# Ethernet3.net
KiCad netlist of a schematic drawn in Altium Designer
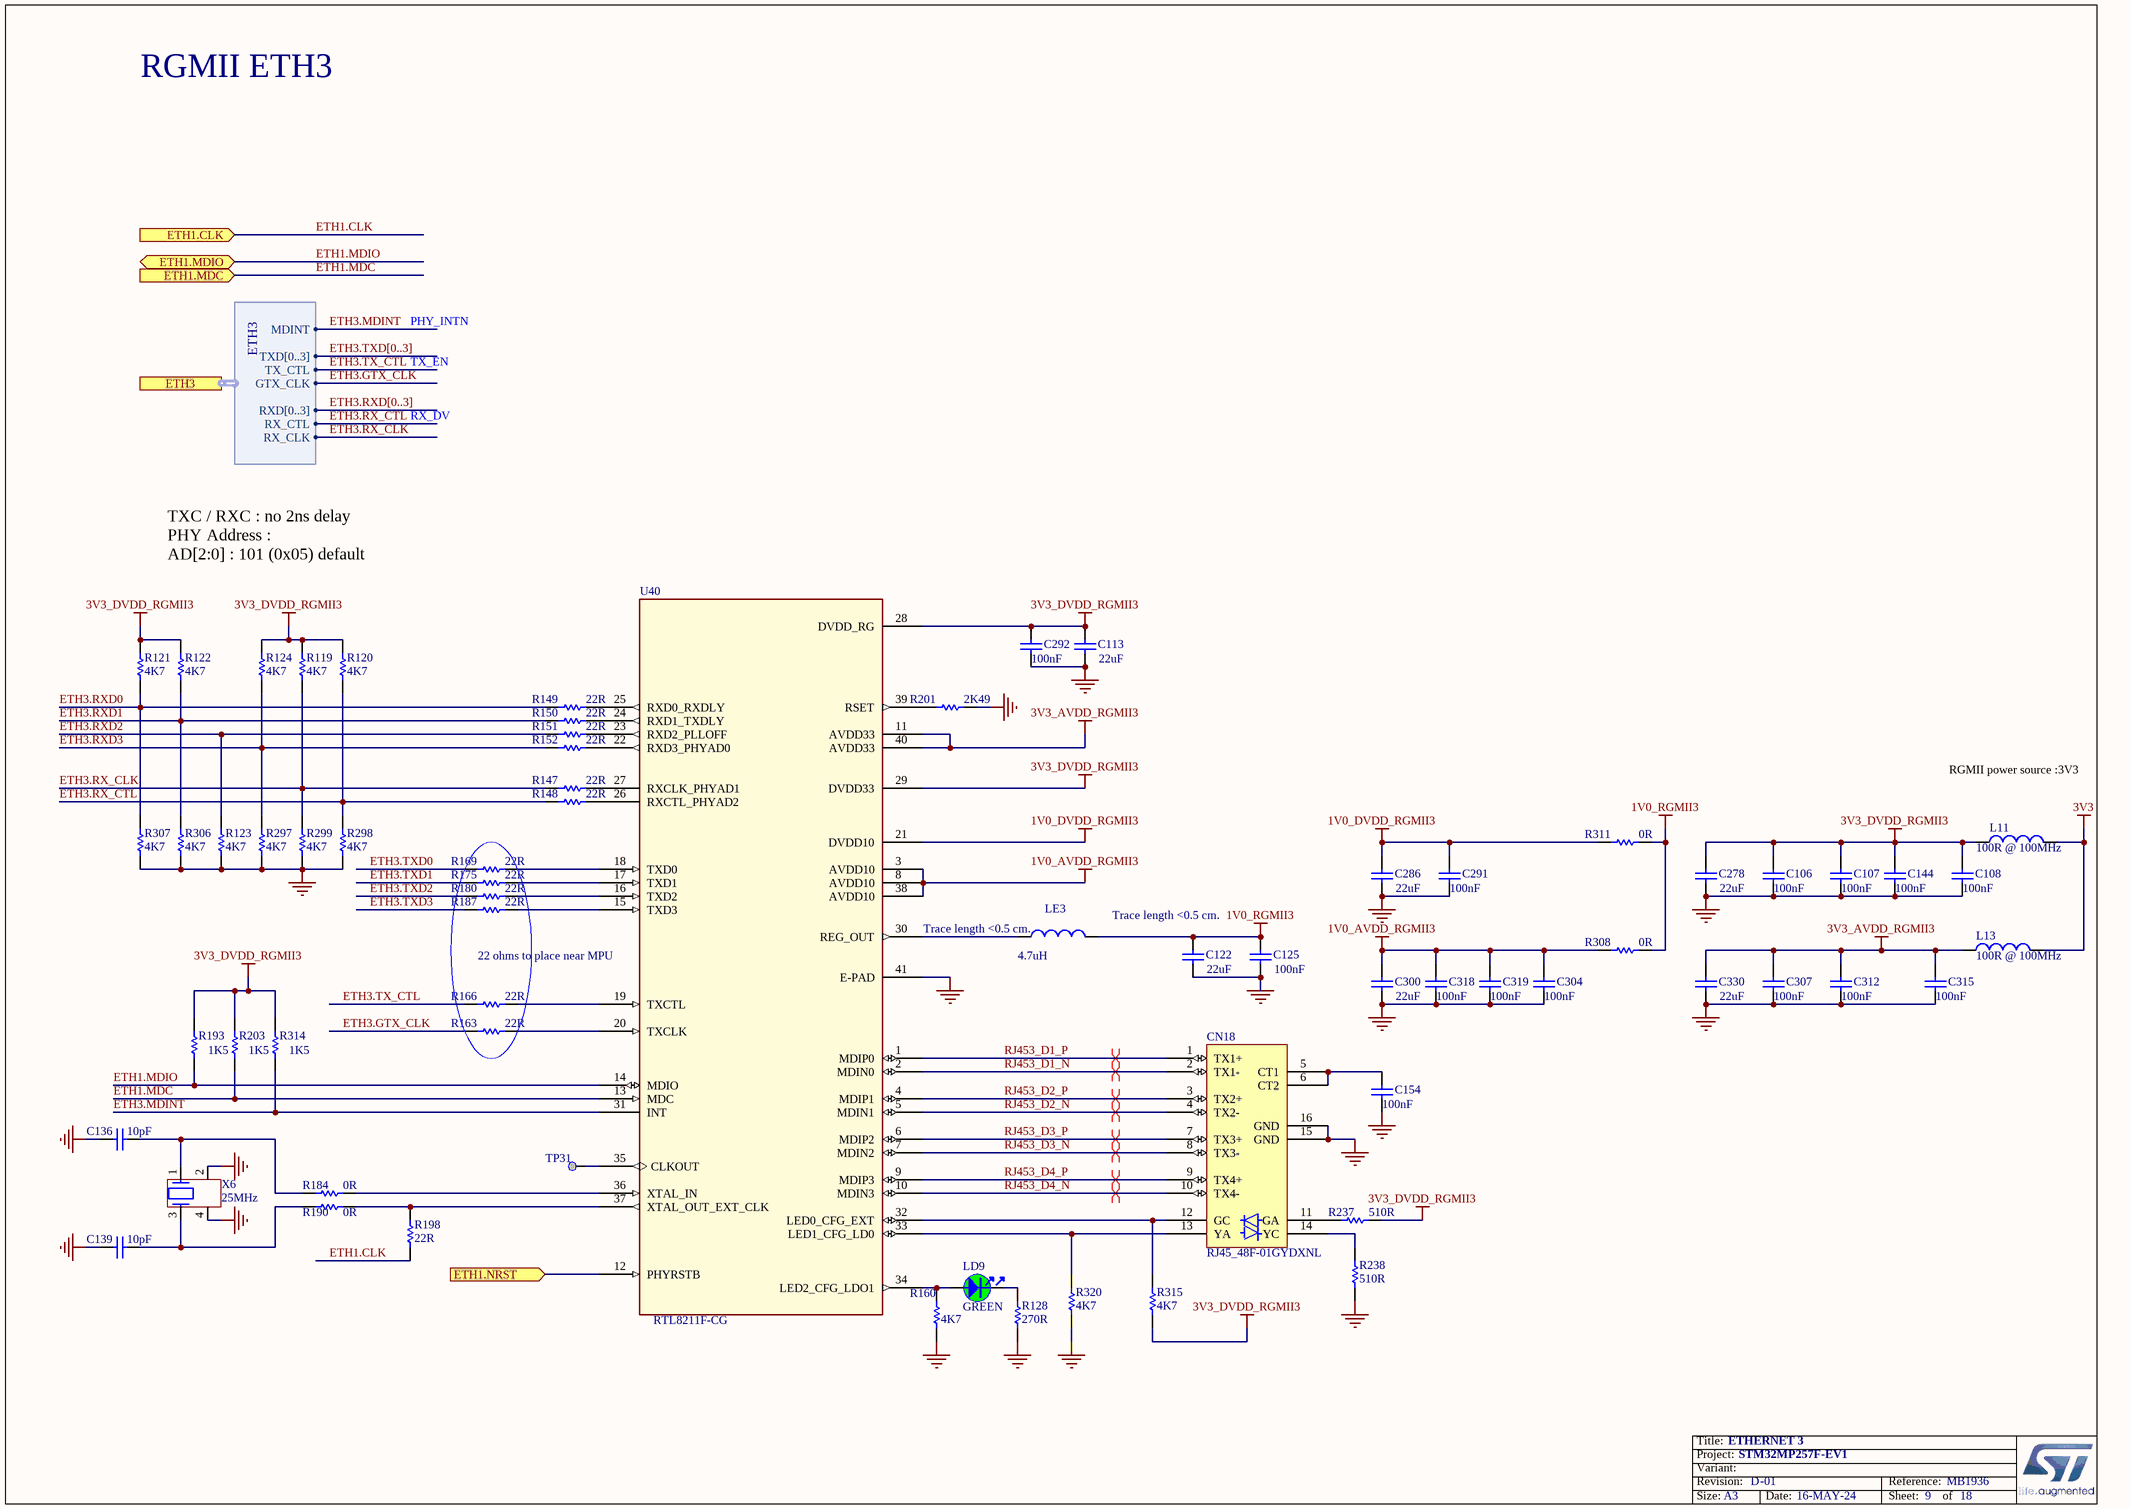
[diagram p0: Ethernet3.SchDoc]

(export (version "E")
  (design (tool "Eeschema 10.0.6"))
  (components
    (comp (ref "C106")
      (value "100nF")
      (footprint "MCD_PARTS:C0402")
      (description "Capacitor,100nF,16V,X7R,10%,0402")
      (fields
        (field (name "INTERNAL_PART_NUMBER") "MCD-00006")
        (field (name "MANUFACTURER_PART_NUMBER") "CC0402KRX7R7BB104")
        (field (name "PROVIDED_BY") "SUBCO")
      )
      (libsource (lib "MCD_PARTS_database") (part "Capacitor"))
    )
    (comp (ref "C107")
      (value "100nF")
      (footprint "MCD_PARTS:C0402")
      (description "Capacitor,100nF,16V,X7R,10%,0402")
      (fields
        (field (name "INTERNAL_PART_NUMBER") "MCD-00006")
        (field (name "MANUFACTURER_PART_NUMBER") "CC0402KRX7R7BB104")
        (field (name "PROVIDED_BY") "SUBCO")
      )
      (libsource (lib "MCD_PARTS_database") (part "Capacitor"))
    )
    (comp (ref "C108")
      (value "100nF")
      (footprint "MCD_PARTS:C0402")
      (description "Capacitor,100nF,16V,X7R,10%,0402")
      (fields
        (field (name "INTERNAL_PART_NUMBER") "MCD-00006")
        (field (name "MANUFACTURER_PART_NUMBER") "CC0402KRX7R7BB104")
        (field (name "PROVIDED_BY") "SUBCO")
      )
      (libsource (lib "MCD_PARTS_database") (part "Capacitor"))
    )
    (comp (ref "C113")
      (value "22uF")
      (footprint "MCD_PARTS:C0603")
      (description "Capacitor,22uF,6V3,X5R,20%,0603")
      (fields
        (field (name "INTERNAL_PART_NUMBER") "MCD-00100")
        (field (name "MANUFACTURER_PART_NUMBER") "GRM188R60J226MEA0J")
        (field (name "PROVIDED_BY") "SUBCO")
      )
      (libsource (lib "MCD_PARTS_database") (part "Capacitor"))
    )
    (comp (ref "C122")
      (value "22uF")
      (footprint "MCD_PARTS:C0603")
      (description "Capacitor,22uF,6V3,X5R,20%,0603")
      (fields
        (field (name "INTERNAL_PART_NUMBER") "MCD-00100")
        (field (name "MANUFACTURER_PART_NUMBER") "GRM188R60J226MEA0J")
        (field (name "PROVIDED_BY") "SUBCO")
      )
      (libsource (lib "MCD_PARTS_database") (part "Capacitor"))
    )
    (comp (ref "C125")
      (value "100nF")
      (footprint "MCD_PARTS:C0402")
      (description "Capacitor,100nF,16V,X7R,10%,0402")
      (fields
        (field (name "INTERNAL_PART_NUMBER") "MCD-00006")
        (field (name "MANUFACTURER_PART_NUMBER") "CC0402KRX7R7BB104")
        (field (name "PROVIDED_BY") "SUBCO")
      )
      (libsource (lib "MCD_PARTS_database") (part "Capacitor"))
    )
    (comp (ref "C136")
      (value "10pF")
      (footprint "MCD_PARTS:C0402")
      (description "Capacitor,10pF,50V,NPO,5%,0402")
      (fields
        (field (name "INTERNAL_PART_NUMBER") "MCD-00015")
        (field (name "MANUFACTURER_PART_NUMBER") "CC0402JRNPO9BN100")
        (field (name "PROVIDED_BY") "SUBCO")
      )
      (libsource (lib "MCD_PARTS_database") (part "Capacitor"))
    )
    (comp (ref "C139")
      (value "10pF")
      (footprint "MCD_PARTS:C0402")
      (description "Capacitor,10pF,50V,NPO,5%,0402")
      (fields
        (field (name "INTERNAL_PART_NUMBER") "MCD-00015")
        (field (name "MANUFACTURER_PART_NUMBER") "CC0402JRNPO9BN100")
        (field (name "PROVIDED_BY") "SUBCO")
      )
      (libsource (lib "MCD_PARTS_database") (part "Capacitor"))
    )
    (comp (ref "C144")
      (value "100nF")
      (footprint "MCD_PARTS:C0402")
      (description "Capacitor,100nF,16V,X7R,10%,0402")
      (fields
        (field (name "INTERNAL_PART_NUMBER") "MCD-00006")
        (field (name "MANUFACTURER_PART_NUMBER") "CC0402KRX7R7BB104")
        (field (name "PROVIDED_BY") "SUBCO")
      )
      (libsource (lib "MCD_PARTS_database") (part "Capacitor"))
    )
    (comp (ref "C154")
      (value "100nF")
      (footprint "MCD_PARTS:C0402")
      (description "Capacitor,100nF,16V,X7R,10%,0402")
      (fields
        (field (name "INTERNAL_PART_NUMBER") "MCD-00006")
        (field (name "MANUFACTURER_PART_NUMBER") "CC0402KRX7R7BB104")
        (field (name "PROVIDED_BY") "SUBCO")
      )
      (libsource (lib "MCD_PARTS_database") (part "Capacitor"))
    )
    (comp (ref "C278")
      (value "22uF")
      (footprint "MCD_PARTS:C0603")
      (description "Capacitor,22uF,6V3,X5R,20%,0603")
      (fields
        (field (name "INTERNAL_PART_NUMBER") "MCD-00100")
        (field (name "MANUFACTURER_PART_NUMBER") "GRM188R60J226MEA0J")
        (field (name "PROVIDED_BY") "SUBCO")
      )
      (libsource (lib "MCD_PARTS_database") (part "Capacitor"))
    )
    (comp (ref "C286")
      (value "22uF")
      (footprint "MCD_PARTS:C0603")
      (description "Capacitor,22uF,6V3,X5R,20%,0603")
      (fields
        (field (name "INTERNAL_PART_NUMBER") "MCD-00100")
        (field (name "MANUFACTURER_PART_NUMBER") "GRM188R60J226MEA0J")
        (field (name "PROVIDED_BY") "SUBCO")
      )
      (libsource (lib "MCD_PARTS_database") (part "Capacitor"))
    )
    (comp (ref "C291")
      (value "100nF")
      (footprint "MCD_PARTS:C0402")
      (description "Capacitor,100nF,16V,X7R,10%,0402")
      (fields
        (field (name "INTERNAL_PART_NUMBER") "MCD-00006")
        (field (name "MANUFACTURER_PART_NUMBER") "CC0402KRX7R7BB104")
        (field (name "PROVIDED_BY") "SUBCO")
      )
      (libsource (lib "MCD_PARTS_database") (part "Capacitor"))
    )
    (comp (ref "C292")
      (value "100nF")
      (footprint "MCD_PARTS:C0402")
      (description "Capacitor,100nF,16V,X7R,10%,0402")
      (fields
        (field (name "INTERNAL_PART_NUMBER") "MCD-00006")
        (field (name "MANUFACTURER_PART_NUMBER") "CC0402KRX7R7BB104")
        (field (name "PROVIDED_BY") "SUBCO")
      )
      (libsource (lib "MCD_PARTS_database") (part "Capacitor"))
    )
    (comp (ref "C300")
      (value "22uF")
      (footprint "MCD_PARTS:C0603")
      (description "Capacitor,22uF,6V3,X5R,20%,0603")
      (fields
        (field (name "INTERNAL_PART_NUMBER") "MCD-00100")
        (field (name "MANUFACTURER_PART_NUMBER") "GRM188R60J226MEA0J")
        (field (name "PROVIDED_BY") "SUBCO")
      )
      (libsource (lib "MCD_PARTS_database") (part "Capacitor"))
    )
    (comp (ref "C304")
      (value "100nF")
      (footprint "MCD_PARTS:C0402")
      (description "Capacitor,100nF,16V,X7R,10%,0402")
      (fields
        (field (name "INTERNAL_PART_NUMBER") "MCD-00006")
        (field (name "MANUFACTURER_PART_NUMBER") "CC0402KRX7R7BB104")
        (field (name "PROVIDED_BY") "SUBCO")
      )
      (libsource (lib "MCD_PARTS_database") (part "Capacitor"))
    )
    (comp (ref "C307")
      (value "100nF")
      (footprint "MCD_PARTS:C0402")
      (description "Capacitor,100nF,16V,X7R,10%,0402")
      (fields
        (field (name "INTERNAL_PART_NUMBER") "MCD-00006")
        (field (name "MANUFACTURER_PART_NUMBER") "CC0402KRX7R7BB104")
        (field (name "PROVIDED_BY") "SUBCO")
      )
      (libsource (lib "MCD_PARTS_database") (part "Capacitor"))
    )
    (comp (ref "C312")
      (value "100nF")
      (footprint "MCD_PARTS:C0402")
      (description "Capacitor,100nF,16V,X7R,10%,0402")
      (fields
        (field (name "INTERNAL_PART_NUMBER") "MCD-00006")
        (field (name "MANUFACTURER_PART_NUMBER") "CC0402KRX7R7BB104")
        (field (name "PROVIDED_BY") "SUBCO")
      )
      (libsource (lib "MCD_PARTS_database") (part "Capacitor"))
    )
    (comp (ref "C315")
      (value "100nF")
      (footprint "MCD_PARTS:C0402")
      (description "Capacitor,100nF,16V,X7R,10%,0402")
      (fields
        (field (name "INTERNAL_PART_NUMBER") "MCD-00006")
        (field (name "MANUFACTURER_PART_NUMBER") "CC0402KRX7R7BB104")
        (field (name "PROVIDED_BY") "SUBCO")
      )
      (libsource (lib "MCD_PARTS_database") (part "Capacitor"))
    )
    (comp (ref "C318")
      (value "100nF")
      (footprint "MCD_PARTS:C0402")
      (description "Capacitor,100nF,16V,X7R,10%,0402")
      (fields
        (field (name "INTERNAL_PART_NUMBER") "MCD-00006")
        (field (name "MANUFACTURER_PART_NUMBER") "CC0402KRX7R7BB104")
        (field (name "PROVIDED_BY") "SUBCO")
      )
      (libsource (lib "MCD_PARTS_database") (part "Capacitor"))
    )
    (comp (ref "C319")
      (value "100nF")
      (footprint "MCD_PARTS:C0402")
      (description "Capacitor,100nF,16V,X7R,10%,0402")
      (fields
        (field (name "INTERNAL_PART_NUMBER") "MCD-00006")
        (field (name "MANUFACTURER_PART_NUMBER") "CC0402KRX7R7BB104")
        (field (name "PROVIDED_BY") "SUBCO")
      )
      (libsource (lib "MCD_PARTS_database") (part "Capacitor"))
    )
    (comp (ref "C330")
      (value "22uF")
      (footprint "MCD_PARTS:C0603")
      (description "Capacitor,22uF,6V3,X5R,20%,0603")
      (fields
        (field (name "INTERNAL_PART_NUMBER") "MCD-00100")
        (field (name "MANUFACTURER_PART_NUMBER") "GRM188R60J226MEA0J")
        (field (name "PROVIDED_BY") "SUBCO")
      )
      (libsource (lib "MCD_PARTS_database") (part "Capacitor"))
    )
    (comp (ref "CN18")
      (value "RJ45_48F-01GYDXNL")
      (footprint "MCD_PARTS:CON_RJ45_YD_48F-01GYDXNL_LED-P")
      (description "Connector_RJ45, led pull down, T= 13.84mm")
      (fields
        (field (name "INTERNAL_PART_NUMBER") "MCD-01129")
        (field (name "MANUFACTURER_PART_NUMBER") "48F-01GYDXNL")
      )
      (libsource (lib "MCD_PARTS_database") (part "RJ45_48F_01GYDXNL_LPD"))
    )
    (comp (ref "L11")
      (value "100R @ 100MHz")
      (footprint "MCD_PARTS:FIL_0603_H0P65")
      (description "Ferrite bead 100R 2A 0603")
      (fields
        (field (name "INTERNAL_PART_NUMBER") "MCD-00094")
        (field (name "MANUFACTURER_PART_NUMBER") "BLM18EG101TN1")
        (field (name "PROVIDED_BY") "SUBCO")
      )
      (libsource (lib "MCD_PARTS_database") (part "BEAD"))
    )
    (comp (ref "L13")
      (value "100R @ 100MHz")
      (footprint "MCD_PARTS:FIL_0603_H0P65")
      (description "Ferrite bead 100R 2A 0603")
      (fields
        (field (name "INTERNAL_PART_NUMBER") "MCD-00094")
        (field (name "MANUFACTURER_PART_NUMBER") "BLM18EG101TN1")
        (field (name "PROVIDED_BY") "SUBCO")
      )
      (libsource (lib "MCD_PARTS_database") (part "BEAD"))
    )
    (comp (ref "LD9")
      (value "GREEN")
      (footprint "MCD_PARTS:LED_0603_OSRAM_LG-Q396-PS-35_GREEN_1A2K_H0P4")
      (description "LED Green, 0603 SMD, Forward Voltage Typ=2V, Max=2.5V")
      (fields
        (field (name "INTERNAL_PART_NUMBER") "MCD-00588")
        (field (name "MANUFACTURER_PART_NUMBER") "LG Q396-PS-35")
        (field (name "PROVIDED_BY") "SUBCO")
      )
      (libsource (lib "MCD_PARTS_database") (part "LED_green"))
    )
    (comp (ref "LE3")
      (value "4.7uH")
      (footprint "MCD_PARTS:L1210_LQH")
      (description "FIXED IND 4.7UH 1A 180 MOHM 30% SMD")
      (fields
        (field (name "INTERNAL_PART_NUMBER") "MCD-00048")
        (field (name "MANUFACTURER_PART_NUMBER") "LQH32PN4R7NN0L")
        (field (name "PROVIDED_BY") "SUBCO")
      )
      (libsource (lib "MCD_PARTS_database") (part "Inductor"))
    )
    (comp (ref "R119")
      (value "4K7")
      (footprint "MCD_PARTS:R0402")
      (description "Resistor,4K7,0402,1%,1/16W")
      (fields
        (field (name "INTERNAL_PART_NUMBER") "MCD-00065")
        (field (name "MANUFACTURER_PART_NUMBER") "RC0402FR-074K7L")
        (field (name "PROVIDED_BY") "SUBCO")
      )
      (libsource (lib "MCD_PARTS_database") (part "Resistor"))
    )
    (comp (ref "R120")
      (value "4K7")
      (footprint "MCD_PARTS:R0402")
      (description "Resistor,4K7,0402,1%,1/16W")
      (fields
        (field (name "INTERNAL_PART_NUMBER") "MCD-00065")
        (field (name "MANUFACTURER_PART_NUMBER") "RC0402FR-074K7L")
        (field (name "PROVIDED_BY") "SUBCO")
      )
      (libsource (lib "MCD_PARTS_database") (part "Resistor"))
    )
    (comp (ref "R121")
      (value "4K7")
      (footprint "MCD_PARTS:R0402")
      (description "Resistor,4K7,0402,1%,1/16W")
      (fields
        (field (name "INTERNAL_PART_NUMBER") "MCD-00065")
        (field (name "MANUFACTURER_PART_NUMBER") "RC0402FR-074K7L")
        (field (name "PROVIDED_BY") "SUBCO")
      )
      (libsource (lib "MCD_PARTS_database") (part "Resistor"))
    )
    (comp (ref "R122")
      (value "4K7")
      (footprint "MCD_PARTS:R0402")
      (description "Resistor,4K7,0402,1%,1/16W")
      (fields
        (field (name "INTERNAL_PART_NUMBER") "MCD-00065")
        (field (name "MANUFACTURER_PART_NUMBER") "RC0402FR-074K7L")
        (field (name "PROVIDED_BY") "SUBCO")
      )
      (libsource (lib "MCD_PARTS_database") (part "Resistor"))
    )
    (comp (ref "R123")
      (value "4K7")
      (footprint "MCD_PARTS:R0402")
      (description "Resistor,4K7,0402,1%,1/16W")
      (fields
        (field (name "INTERNAL_PART_NUMBER") "MCD-00065")
        (field (name "MANUFACTURER_PART_NUMBER") "RC0402FR-074K7L")
        (field (name "PROVIDED_BY") "SUBCO")
      )
      (libsource (lib "MCD_PARTS_database") (part "Resistor"))
    )
    (comp (ref "R124")
      (value "4K7")
      (footprint "MCD_PARTS:R0402")
      (description "Resistor,4K7,0402,1%,1/16W")
      (fields
        (field (name "INTERNAL_PART_NUMBER") "MCD-00065")
        (field (name "MANUFACTURER_PART_NUMBER") "RC0402FR-074K7L")
        (field (name "PROVIDED_BY") "SUBCO")
      )
      (libsource (lib "MCD_PARTS_database") (part "Resistor"))
    )
    (comp (ref "R128")
      (value "270R")
      (footprint "MCD_PARTS:R0402")
      (description "Resistor,270R,0402,1%,1/16W")
      (fields
        (field (name "INTERNAL_PART_NUMBER") "MCD-00441")
        (field (name "MANUFACTURER_PART_NUMBER") "RC0402FR-07270RL")
        (field (name "PROVIDED_BY") "SUBCO")
      )
      (libsource (lib "MCD_PARTS_database") (part "Resistor"))
    )
    (comp (ref "R147")
      (value "22R")
      (footprint "MCD_PARTS:R0201_H0P23")
      (description "Resistor, 22R, 0201, +/-1%, 1/20W")
      (fields
        (field (name "INTERNAL_PART_NUMBER") "MCD-02978")
        (field (name "MANUFACTURER_PART_NUMBER") "RC0201FR-0722RL")
      )
      (libsource (lib "MCD_PARTS_database") (part "Resistor"))
    )
    (comp (ref "R148")
      (value "22R")
      (footprint "MCD_PARTS:R0201_H0P23")
      (description "Resistor, 22R, 0201, +/-1%, 1/20W")
      (fields
        (field (name "INTERNAL_PART_NUMBER") "MCD-02978")
        (field (name "MANUFACTURER_PART_NUMBER") "RC0201FR-0722RL")
      )
      (libsource (lib "MCD_PARTS_database") (part "Resistor"))
    )
    (comp (ref "R149")
      (value "22R")
      (footprint "MCD_PARTS:R0201_H0P23")
      (description "Resistor, 22R, 0201, +/-1%, 1/20W")
      (fields
        (field (name "INTERNAL_PART_NUMBER") "MCD-02978")
        (field (name "MANUFACTURER_PART_NUMBER") "RC0201FR-0722RL")
      )
      (libsource (lib "MCD_PARTS_database") (part "Resistor"))
    )
    (comp (ref "R150")
      (value "22R")
      (footprint "MCD_PARTS:R0201_H0P23")
      (description "Resistor, 22R, 0201, +/-1%, 1/20W")
      (fields
        (field (name "INTERNAL_PART_NUMBER") "MCD-02978")
        (field (name "MANUFACTURER_PART_NUMBER") "RC0201FR-0722RL")
      )
      (libsource (lib "MCD_PARTS_database") (part "Resistor"))
    )
    (comp (ref "R151")
      (value "22R")
      (footprint "MCD_PARTS:R0201_H0P23")
      (description "Resistor, 22R, 0201, +/-1%, 1/20W")
      (fields
        (field (name "INTERNAL_PART_NUMBER") "MCD-02978")
        (field (name "MANUFACTURER_PART_NUMBER") "RC0201FR-0722RL")
      )
      (libsource (lib "MCD_PARTS_database") (part "Resistor"))
    )
    (comp (ref "R152")
      (value "22R")
      (footprint "MCD_PARTS:R0201_H0P23")
      (description "Resistor, 22R, 0201, +/-1%, 1/20W")
      (fields
        (field (name "INTERNAL_PART_NUMBER") "MCD-02978")
        (field (name "MANUFACTURER_PART_NUMBER") "RC0201FR-0722RL")
      )
      (libsource (lib "MCD_PARTS_database") (part "Resistor"))
    )
    (comp (ref "R160")
      (value "4K7")
      (footprint "MCD_PARTS:R0402")
      (description "Resistor,4K7,0402,1%,1/16W")
      (fields
        (field (name "INTERNAL_PART_NUMBER") "MCD-00065")
        (field (name "MANUFACTURER_PART_NUMBER") "RC0402FR-074K7L")
        (field (name "PROVIDED_BY") "SUBCO")
      )
      (libsource (lib "MCD_PARTS_database") (part "Resistor"))
    )
    (comp (ref "R163")
      (value "22R")
      (footprint "MCD_PARTS:R0201_H0P23")
      (description "Resistor, 22R, 0201, +/-1%, 1/20W")
      (fields
        (field (name "INTERNAL_PART_NUMBER") "MCD-02978")
        (field (name "MANUFACTURER_PART_NUMBER") "RC0201FR-0722RL")
      )
      (libsource (lib "MCD_PARTS_database") (part "Resistor"))
    )
    (comp (ref "R166")
      (value "22R")
      (footprint "MCD_PARTS:R0201_H0P23")
      (description "Resistor, 22R, 0201, +/-1%, 1/20W")
      (fields
        (field (name "INTERNAL_PART_NUMBER") "MCD-02978")
        (field (name "MANUFACTURER_PART_NUMBER") "RC0201FR-0722RL")
      )
      (libsource (lib "MCD_PARTS_database") (part "Resistor"))
    )
    (comp (ref "R169")
      (value "22R")
      (footprint "MCD_PARTS:R0201_H0P23")
      (description "Resistor, 22R, 0201, +/-1%, 1/20W")
      (fields
        (field (name "INTERNAL_PART_NUMBER") "MCD-02978")
        (field (name "MANUFACTURER_PART_NUMBER") "RC0201FR-0722RL")
      )
      (libsource (lib "MCD_PARTS_database") (part "Resistor"))
    )
    (comp (ref "R175")
      (value "22R")
      (footprint "MCD_PARTS:R0201_H0P23")
      (description "Resistor, 22R, 0201, +/-1%, 1/20W")
      (fields
        (field (name "INTERNAL_PART_NUMBER") "MCD-02978")
        (field (name "MANUFACTURER_PART_NUMBER") "RC0201FR-0722RL")
      )
      (libsource (lib "MCD_PARTS_database") (part "Resistor"))
    )
    (comp (ref "R180")
      (value "22R")
      (footprint "MCD_PARTS:R0201_H0P23")
      (description "Resistor, 22R, 0201, +/-1%, 1/20W")
      (fields
        (field (name "INTERNAL_PART_NUMBER") "MCD-02978")
        (field (name "MANUFACTURER_PART_NUMBER") "RC0201FR-0722RL")
      )
      (libsource (lib "MCD_PARTS_database") (part "Resistor"))
    )
    (comp (ref "R184")
      (value "0R")
      (footprint "MCD_PARTS:R0402")
      (description "Resistor,0R,0402,5%,1/16W")
      (fields
        (field (name "INTERNAL_PART_NUMBER") "MCD-00052")
        (field (name "MANUFACTURER_PART_NUMBER") "RC0402JR-070RL")
        (field (name "PROVIDED_BY") "SUBCO")
      )
      (libsource (lib "MCD_PARTS_database") (part "Resistor"))
    )
    (comp (ref "R187")
      (value "22R")
      (footprint "MCD_PARTS:R0201_H0P23")
      (description "Resistor, 22R, 0201, +/-1%, 1/20W")
      (fields
        (field (name "INTERNAL_PART_NUMBER") "MCD-02978")
        (field (name "MANUFACTURER_PART_NUMBER") "RC0201FR-0722RL")
      )
      (libsource (lib "MCD_PARTS_database") (part "Resistor"))
    )
    (comp (ref "R190")
      (value "0R")
      (footprint "MCD_PARTS:R0402")
      (description "Resistor,0R,0402,5%,1/16W")
      (fields
        (field (name "INTERNAL_PART_NUMBER") "MCD-00052")
        (field (name "MANUFACTURER_PART_NUMBER") "RC0402JR-070RL")
        (field (name "PROVIDED_BY") "SUBCO")
      )
      (libsource (lib "MCD_PARTS_database") (part "Resistor"))
    )
    (comp (ref "R193")
      (value "1K5")
      (footprint "MCD_PARTS:R0402")
      (description "Resistor,1K5,0402,1%,1/16W")
      (fields
        (field (name "INTERNAL_PART_NUMBER") "MCD-00068")
        (field (name "MANUFACTURER_PART_NUMBER") "RC0402FR-071K5L")
        (field (name "PROVIDED_BY") "SUBCO")
      )
      (libsource (lib "MCD_PARTS_database") (part "Resistor"))
    )
    (comp (ref "R198")
      (value "22R")
      (footprint "MCD_PARTS:R0201_H0P23")
      (description "Resistor, 22R, 0201, +/-1%, 1/20W")
      (fields
        (field (name "INTERNAL_PART_NUMBER") "MCD-02978")
        (field (name "MANUFACTURER_PART_NUMBER") "RC0201FR-0722RL")
      )
      (libsource (lib "MCD_PARTS_database") (part "Resistor"))
    )
    (comp (ref "R201")
      (value "2K49")
      (footprint "MCD_PARTS:R0402")
      (description "Resistor,2K49,0402,1%,1/16W")
      (fields
        (field (name "INTERNAL_PART_NUMBER") "MCD-00183")
        (field (name "MANUFACTURER_PART_NUMBER") "RC0402FR-072K49L")
        (field (name "PROVIDED_BY") "SUBCO")
      )
      (libsource (lib "MCD_PARTS_database") (part "Resistor"))
    )
    (comp (ref "R203")
      (value "1K5")
      (footprint "MCD_PARTS:R0402")
      (description "Resistor,1K5,0402,1%,1/16W")
      (fields
        (field (name "INTERNAL_PART_NUMBER") "MCD-00068")
        (field (name "MANUFACTURER_PART_NUMBER") "RC0402FR-071K5L")
        (field (name "PROVIDED_BY") "SUBCO")
      )
      (libsource (lib "MCD_PARTS_database") (part "Resistor"))
    )
    (comp (ref "R237")
      (value "510R")
      (footprint "MCD_PARTS:R0402")
      (description "Resistor,510R,0402,1%,1/16W")
      (fields
        (field (name "INTERNAL_PART_NUMBER") "MCD-00064")
        (field (name "MANUFACTURER_PART_NUMBER") "RC0402FR-07510RL")
        (field (name "PROVIDED_BY") "SUBCO")
      )
      (libsource (lib "MCD_PARTS_database") (part "Resistor"))
    )
    (comp (ref "R238")
      (value "510R")
      (footprint "MCD_PARTS:R0402")
      (description "Resistor,510R,0402,1%,1/16W")
      (fields
        (field (name "INTERNAL_PART_NUMBER") "MCD-00064")
        (field (name "MANUFACTURER_PART_NUMBER") "RC0402FR-07510RL")
        (field (name "PROVIDED_BY") "SUBCO")
      )
      (libsource (lib "MCD_PARTS_database") (part "Resistor"))
    )
    (comp (ref "R297")
      (value "4K7")
      (footprint "MCD_PARTS:R0402")
      (description "Resistor,4K7,0402,1%,1/16W")
      (fields
        (field (name "INTERNAL_PART_NUMBER") "MCD-00065")
        (field (name "MANUFACTURER_PART_NUMBER") "RC0402FR-074K7L")
        (field (name "PROVIDED_BY") "SUBCO")
      )
      (libsource (lib "MCD_PARTS_database") (part "Resistor"))
    )
    (comp (ref "R298")
      (value "4K7")
      (footprint "MCD_PARTS:R0402")
      (description "Resistor,4K7,0402,1%,1/16W")
      (fields
        (field (name "INTERNAL_PART_NUMBER") "MCD-00065")
        (field (name "MANUFACTURER_PART_NUMBER") "RC0402FR-074K7L")
        (field (name "PROVIDED_BY") "SUBCO")
      )
      (libsource (lib "MCD_PARTS_database") (part "Resistor"))
    )
    (comp (ref "R299")
      (value "4K7")
      (footprint "MCD_PARTS:R0402")
      (description "Resistor,4K7,0402,1%,1/16W")
      (fields
        (field (name "INTERNAL_PART_NUMBER") "MCD-00065")
        (field (name "MANUFACTURER_PART_NUMBER") "RC0402FR-074K7L")
        (field (name "PROVIDED_BY") "SUBCO")
      )
      (libsource (lib "MCD_PARTS_database") (part "Resistor"))
    )
    (comp (ref "R306")
      (value "4K7")
      (footprint "MCD_PARTS:R0402")
      (description "Resistor,4K7,0402,1%,1/16W")
      (fields
        (field (name "INTERNAL_PART_NUMBER") "MCD-00065")
        (field (name "MANUFACTURER_PART_NUMBER") "RC0402FR-074K7L")
        (field (name "PROVIDED_BY") "SUBCO")
      )
      (libsource (lib "MCD_PARTS_database") (part "Resistor"))
    )
    (comp (ref "R307")
      (value "4K7")
      (footprint "MCD_PARTS:R0402")
      (description "Resistor,4K7,0402,1%,1/16W")
      (fields
        (field (name "INTERNAL_PART_NUMBER") "MCD-00065")
        (field (name "MANUFACTURER_PART_NUMBER") "RC0402FR-074K7L")
        (field (name "PROVIDED_BY") "SUBCO")
      )
      (libsource (lib "MCD_PARTS_database") (part "Resistor"))
    )
    (comp (ref "R308")
      (value "0R")
      (footprint "MCD_PARTS:R0603")
      (description "Resistor,0R,0603,5%,1/10W")
      (fields
        (field (name "INTERNAL_PART_NUMBER") "MCD-00056")
        (field (name "MANUFACTURER_PART_NUMBER") "RC0603JR-070RL")
        (field (name "PROVIDED_BY") "SUBCO")
      )
      (libsource (lib "MCD_PARTS_database") (part "Resistor"))
    )
    (comp (ref "R311")
      (value "0R")
      (footprint "MCD_PARTS:R0603")
      (description "Resistor,0R,0603,5%,1/10W")
      (fields
        (field (name "INTERNAL_PART_NUMBER") "MCD-00056")
        (field (name "MANUFACTURER_PART_NUMBER") "RC0603JR-070RL")
        (field (name "PROVIDED_BY") "SUBCO")
      )
      (libsource (lib "MCD_PARTS_database") (part "Resistor"))
    )
    (comp (ref "R314")
      (value "1K5")
      (footprint "MCD_PARTS:R0402")
      (description "Resistor,1K5,0402,1%,1/16W")
      (fields
        (field (name "INTERNAL_PART_NUMBER") "MCD-00068")
        (field (name "MANUFACTURER_PART_NUMBER") "RC0402FR-071K5L")
        (field (name "PROVIDED_BY") "SUBCO")
      )
      (libsource (lib "MCD_PARTS_database") (part "Resistor"))
    )
    (comp (ref "R315")
      (value "4K7")
      (footprint "MCD_PARTS:R0402")
      (description "Resistor,4K7,0402,1%,1/16W")
      (fields
        (field (name "INTERNAL_PART_NUMBER") "MCD-00065")
        (field (name "MANUFACTURER_PART_NUMBER") "RC0402FR-074K7L")
        (field (name "PROVIDED_BY") "SUBCO")
      )
      (libsource (lib "MCD_PARTS_database") (part "Resistor"))
    )
    (comp (ref "R320")
      (value "4K7")
      (footprint "MCD_PARTS:R0402")
      (description "Resistor,4K7,0402,1%,1/16W")
      (fields
        (field (name "INTERNAL_PART_NUMBER") "MCD-00065")
        (field (name "MANUFACTURER_PART_NUMBER") "RC0402FR-074K7L")
        (field (name "PROVIDED_BY") "SUBCO")
      )
      (libsource (lib "MCD_PARTS_database") (part "Resistor"))
    )
    (comp (ref "TP31")
      (value "Test Point")
      (footprint "MCD_PARTS:TP_SMD_1MM")
      (description "Test Point 1mm")
      (fields
        (field (name "INTERNAL_PART_NUMBER") "MCD-00074")
        (field (name "MANUFACTURER_PART_NUMBER") "n/a")
      )
      (libsource (lib "MCD_PARTS_database") (part "Test Point"))
    )
    (comp (ref "U40")
      (value "RTL8211F-CG")
      (footprint "MCD_PARTS:ICC_QFN40-EPAD_5X5_P040")
      (description "10/100/1000M GIGABIT Ethernet Transceiver, QFN40 , SMPS version")
      (fields
        (field (name "INTERNAL_PART_NUMBER") "MCD-01130")
        (field (name "MANUFACTURER") "REALTEK")
        (field (name "PROVIDED_BY") "SUBCO")
      )
      (libsource (lib "MCD_PARTS_database") (part "RTL8211F-CG"))
    )
    (comp (ref "X6")
      (value "25MHz")
      (footprint "MCD_PARTS:CRY_NX3225HA_4P")
      (description "Crystal 25Mhz, 10pF, -+50PPM, SMD")
      (fields
        (field (name "INTERNAL_PART_NUMBER") "MCD-01463")
        (field (name "MANUFACTURER_PART_NUMBER") "NX3225GA-25MHZ-EXS00A-CG06750")
        (field (name "PROVIDED_BY") "SUBCO")
      )
      (libsource (lib "MCD_PARTS_database") (part "XTAL_4_PINS"))
    )
  )
  (nets
    (net (code "2") (name "/ETH1.CLK") (class "Default")
      (node (ref "R198") (pin "1") (pinfunction "1_1") (pintype "passive"))
    )
    (net (code "3") (name "/ETH1.MDC") (class "Default")
      (node (ref "R203") (pin "1") (pinfunction "1_1") (pintype "passive"))
      (node (ref "U40") (pin "13") (pinfunction "MDC_13") (pintype "input"))
    )
    (net (code "4") (name "/ETH1.MDIO") (class "Default")
      (node (ref "R193") (pin "1") (pinfunction "1_1") (pintype "passive"))
      (node (ref "U40") (pin "14") (pinfunction "MDIO_14") (pintype "bidirectional"))
    )
    (net (code "5") (name "/ETH1.NRST") (class "Default")
      (node (ref "U40") (pin "12") (pinfunction "PHYRSTB_12") (pintype "input"))
    )
    (net (code "6") (name "/ETH3.GTX_CLK") (class "Default")
      (node (ref "R163") (pin "1") (pinfunction "1_1") (pintype "passive"))
    )
    (net (code "7") (name "/ETH3.MDINT") (class "Default")
      (node (ref "R314") (pin "1") (pinfunction "1_1") (pintype "passive"))
      (node (ref "U40") (pin "31") (pinfunction "INT_31") (pintype "passive"))
    )
    (net (code "8") (name "/ETH3.RXD0") (class "Default")
      (node (ref "R121") (pin "1") (pinfunction "1_1") (pintype "passive"))
      (node (ref "R149") (pin "1") (pinfunction "1_1") (pintype "passive"))
      (node (ref "R307") (pin "2") (pinfunction "2_2") (pintype "passive"))
    )
    (net (code "9") (name "/ETH3.RXD1") (class "Default")
      (node (ref "R122") (pin "1") (pinfunction "1_1") (pintype "passive"))
      (node (ref "R150") (pin "1") (pinfunction "1_1") (pintype "passive"))
      (node (ref "R306") (pin "2") (pinfunction "2_2") (pintype "passive"))
    )
    (net (code "10") (name "/ETH3.RXD2") (class "Default")
      (node (ref "R123") (pin "2") (pinfunction "2_2") (pintype "passive"))
      (node (ref "R151") (pin "1") (pinfunction "1_1") (pintype "passive"))
    )
    (net (code "11") (name "/ETH3.RXD3") (class "Default")
      (node (ref "R124") (pin "1") (pinfunction "1_1") (pintype "passive"))
      (node (ref "R152") (pin "1") (pinfunction "1_1") (pintype "passive"))
      (node (ref "R297") (pin "2") (pinfunction "2_2") (pintype "passive"))
    )
    (net (code "13") (name "/ETH3.RX_CLK") (class "Default")
      (node (ref "R119") (pin "1") (pinfunction "1_1") (pintype "passive"))
      (node (ref "R147") (pin "1") (pinfunction "1_1") (pintype "passive"))
      (node (ref "R299") (pin "2") (pinfunction "2_2") (pintype "passive"))
    )
    (net (code "14") (name "/ETH3.RX_CTL") (class "Default")
      (node (ref "R120") (pin "1") (pinfunction "1_1") (pintype "passive"))
      (node (ref "R148") (pin "1") (pinfunction "1_1") (pintype "passive"))
      (node (ref "R298") (pin "2") (pinfunction "2_2") (pintype "passive"))
    )
    (net (code "15") (name "/ETH3.TXD0") (class "Default")
      (node (ref "R169") (pin "1") (pinfunction "1_1") (pintype "passive"))
    )
    (net (code "16") (name "/ETH3.TXD1") (class "Default")
      (node (ref "R175") (pin "1") (pinfunction "1_1") (pintype "passive"))
    )
    (net (code "17") (name "/ETH3.TXD2") (class "Default")
      (node (ref "R180") (pin "1") (pinfunction "1_1") (pintype "passive"))
    )
    (net (code "18") (name "/ETH3.TXD3") (class "Default")
      (node (ref "R187") (pin "1") (pinfunction "1_1") (pintype "passive"))
    )
    (net (code "20") (name "/ETH3.TX_CTL") (class "Default")
      (node (ref "R166") (pin "1") (pinfunction "1_1") (pintype "passive"))
    )
    (net (code "21") (name "/RJ453_D1_N") (class "Default")
      (node (ref "CN18") (pin "2") (pinfunction "TX1-_2") (pintype "bidirectional"))
      (node (ref "U40") (pin "2") (pinfunction "MDIN0_2") (pintype "bidirectional"))
    )
    (net (code "22") (name "/RJ453_D1_P") (class "Default")
      (node (ref "CN18") (pin "1") (pinfunction "TX1+_1") (pintype "bidirectional"))
      (node (ref "U40") (pin "1") (pinfunction "MDIP0_1") (pintype "bidirectional"))
    )
    (net (code "23") (name "/RJ453_D2_N") (class "Default")
      (node (ref "CN18") (pin "4") (pinfunction "TX2-_4") (pintype "bidirectional"))
      (node (ref "U40") (pin "5") (pinfunction "MDIN1_5") (pintype "bidirectional"))
    )
    (net (code "24") (name "/RJ453_D2_P") (class "Default")
      (node (ref "CN18") (pin "3") (pinfunction "TX2+_3") (pintype "bidirectional"))
      (node (ref "U40") (pin "4") (pinfunction "MDIP1_4") (pintype "bidirectional"))
    )
    (net (code "25") (name "/RJ453_D3_N") (class "Default")
      (node (ref "CN18") (pin "8") (pinfunction "TX3-_8") (pintype "bidirectional"))
      (node (ref "U40") (pin "7") (pinfunction "MDIN2_7") (pintype "bidirectional"))
    )
    (net (code "26") (name "/RJ453_D3_P") (class "Default")
      (node (ref "CN18") (pin "7") (pinfunction "TX3+_7") (pintype "bidirectional"))
      (node (ref "U40") (pin "6") (pinfunction "MDIP2_6") (pintype "bidirectional"))
    )
    (net (code "27") (name "/RJ453_D4_N") (class "Default")
      (node (ref "CN18") (pin "10") (pinfunction "TX4-_10") (pintype "bidirectional"))
      (node (ref "U40") (pin "10") (pinfunction "MDIN3_10") (pintype "bidirectional"))
    )
    (net (code "28") (name "/RJ453_D4_P") (class "Default")
      (node (ref "CN18") (pin "9") (pinfunction "TX4+_9") (pintype "bidirectional"))
      (node (ref "U40") (pin "9") (pinfunction "MDIP3_9") (pintype "bidirectional"))
    )
    (net (code "30") (name "1V0_AVDD_RGMII3") (class "Default")
      (node (ref "C300") (pin "2") (pinfunction "2_2") (pintype "passive"))
      (node (ref "C304") (pin "2") (pinfunction "2_2") (pintype "passive"))
      (node (ref "C318") (pin "2") (pinfunction "2_2") (pintype "passive"))
      (node (ref "C319") (pin "2") (pinfunction "2_2") (pintype "passive"))
      (node (ref "R308") (pin "1") (pinfunction "1_1") (pintype "passive"))
      (node (ref "U40") (pin "3") (pinfunction "AVDD10_3") (pintype "power_in"))
      (node (ref "U40") (pin "38") (pinfunction "AVDD10_38") (pintype "power_in"))
      (node (ref "U40") (pin "8") (pinfunction "AVDD10_8") (pintype "power_in"))
    )
    (net (code "31") (name "1V0_DVDD_RGMII3") (class "Default")
      (node (ref "C286") (pin "2") (pinfunction "2_2") (pintype "passive"))
      (node (ref "C291") (pin "2") (pinfunction "2_2") (pintype "passive"))
      (node (ref "R311") (pin "1") (pinfunction "1_1") (pintype "passive"))
      (node (ref "U40") (pin "21") (pinfunction "DVDD10_21") (pintype "power_in"))
    )
    (net (code "32") (name "1V0_RGMII3") (class "Default")
      (node (ref "C122") (pin "2") (pinfunction "2_2") (pintype "passive"))
      (node (ref "C125") (pin "2") (pinfunction "2_2") (pintype "passive"))
      (node (ref "LE3") (pin "2") (pinfunction "2_2") (pintype "passive"))
      (node (ref "R308") (pin "2") (pinfunction "2_2") (pintype "passive"))
      (node (ref "R311") (pin "2") (pinfunction "2_2") (pintype "passive"))
    )
    (net (code "33") (name "3V3") (class "Default")
      (node (ref "L11") (pin "2") (pinfunction "2_2") (pintype "passive"))
      (node (ref "L13") (pin "2") (pinfunction "2_2") (pintype "passive"))
    )
    (net (code "34") (name "3V3_AVDD_RGMII3") (class "Default")
      (node (ref "C307") (pin "2") (pinfunction "2_2") (pintype "passive"))
      (node (ref "C312") (pin "2") (pinfunction "2_2") (pintype "passive"))
      (node (ref "C315") (pin "2") (pinfunction "2_2") (pintype "passive"))
      (node (ref "C330") (pin "2") (pinfunction "2_2") (pintype "passive"))
      (node (ref "L13") (pin "1") (pinfunction "1_1") (pintype "passive"))
      (node (ref "U40") (pin "11") (pinfunction "AVDD33_11") (pintype "power_in"))
      (node (ref "U40") (pin "40") (pinfunction "AVDD33_40") (pintype "power_in"))
    )
    (net (code "35") (name "3V3_DVDD_RGMII3") (class "Default")
      (node (ref "C106") (pin "2") (pinfunction "2_2") (pintype "passive"))
      (node (ref "C107") (pin "2") (pinfunction "2_2") (pintype "passive"))
      (node (ref "C108") (pin "2") (pinfunction "2_2") (pintype "passive"))
      (node (ref "C113") (pin "1") (pinfunction "1_1") (pintype "passive"))
      (node (ref "C144") (pin "2") (pinfunction "2_2") (pintype "passive"))
      (node (ref "C278") (pin "2") (pinfunction "2_2") (pintype "passive"))
      (node (ref "C292") (pin "2") (pinfunction "2_2") (pintype "passive"))
      (node (ref "L11") (pin "1") (pinfunction "1_1") (pintype "passive"))
      (node (ref "R119") (pin "2") (pinfunction "2_2") (pintype "passive"))
      (node (ref "R120") (pin "2") (pinfunction "2_2") (pintype "passive"))
      (node (ref "R121") (pin "2") (pinfunction "2_2") (pintype "passive"))
      (node (ref "R122") (pin "2") (pinfunction "2_2") (pintype "passive"))
      (node (ref "R124") (pin "2") (pinfunction "2_2") (pintype "passive"))
      (node (ref "R193") (pin "2") (pinfunction "2_2") (pintype "passive"))
      (node (ref "R203") (pin "2") (pinfunction "2_2") (pintype "passive"))
      (node (ref "R237") (pin "2") (pinfunction "2_2") (pintype "passive"))
      (node (ref "R314") (pin "2") (pinfunction "2_2") (pintype "passive"))
      (node (ref "R315") (pin "1") (pinfunction "1_1") (pintype "passive"))
      (node (ref "U40") (pin "28") (pinfunction "DVDD_RG_28") (pintype "power_in"))
      (node (ref "U40") (pin "29") (pinfunction "DVDD33_29") (pintype "power_in"))
    )
    (net (code "36") (name "GND") (class "Default")
      (node (ref "C106") (pin "1") (pinfunction "1_1") (pintype "passive"))
      (node (ref "C107") (pin "1") (pinfunction "1_1") (pintype "passive"))
      (node (ref "C108") (pin "1") (pinfunction "1_1") (pintype "passive"))
      (node (ref "C113") (pin "2") (pinfunction "2_2") (pintype "passive"))
      (node (ref "C122") (pin "1") (pinfunction "1_1") (pintype "passive"))
      (node (ref "C125") (pin "1") (pinfunction "1_1") (pintype "passive"))
      (node (ref "C136") (pin "1") (pinfunction "1_1") (pintype "passive"))
      (node (ref "C139") (pin "1") (pinfunction "1_1") (pintype "passive"))
      (node (ref "C144") (pin "1") (pinfunction "1_1") (pintype "passive"))
      (node (ref "C154") (pin "1") (pinfunction "1_1") (pintype "passive"))
      (node (ref "C278") (pin "1") (pinfunction "1_1") (pintype "passive"))
      (node (ref "C286") (pin "1") (pinfunction "1_1") (pintype "passive"))
      (node (ref "C291") (pin "1") (pinfunction "1_1") (pintype "passive"))
      (node (ref "C292") (pin "1") (pinfunction "1_1") (pintype "passive"))
      (node (ref "C300") (pin "1") (pinfunction "1_1") (pintype "passive"))
      (node (ref "C304") (pin "1") (pinfunction "1_1") (pintype "passive"))
      (node (ref "C307") (pin "1") (pinfunction "1_1") (pintype "passive"))
      (node (ref "C312") (pin "1") (pinfunction "1_1") (pintype "passive"))
      (node (ref "C315") (pin "1") (pinfunction "1_1") (pintype "passive"))
      (node (ref "C318") (pin "1") (pinfunction "1_1") (pintype "passive"))
      (node (ref "C319") (pin "1") (pinfunction "1_1") (pintype "passive"))
      (node (ref "C330") (pin "1") (pinfunction "1_1") (pintype "passive"))
      (node (ref "CN18") (pin "15") (pinfunction "GND_15") (pintype "power_in"))
      (node (ref "CN18") (pin "16") (pinfunction "GND_16") (pintype "power_in"))
      (node (ref "R123") (pin "1") (pinfunction "1_1") (pintype "passive"))
      (node (ref "R128") (pin "2") (pinfunction "2_2") (pintype "passive"))
      (node (ref "R160") (pin "1") (pinfunction "1_1") (pintype "passive"))
      (node (ref "R201") (pin "2") (pinfunction "2_2") (pintype "passive"))
      (node (ref "R238") (pin "1") (pinfunction "1_1") (pintype "passive"))
      (node (ref "R297") (pin "1") (pinfunction "1_1") (pintype "passive"))
      (node (ref "R298") (pin "1") (pinfunction "1_1") (pintype "passive"))
      (node (ref "R299") (pin "1") (pinfunction "1_1") (pintype "passive"))
      (node (ref "R306") (pin "1") (pinfunction "1_1") (pintype "passive"))
      (node (ref "R307") (pin "1") (pinfunction "1_1") (pintype "passive"))
      (node (ref "R320") (pin "1") (pinfunction "1_1") (pintype "passive"))
      (node (ref "U40") (pin "41") (pinfunction "E-PAD_41") (pintype "power_in"))
      (node (ref "X6") (pin "2") (pinfunction "2_2") (pintype "passive"))
      (node (ref "X6") (pin "4") (pinfunction "4_4") (pintype "passive"))
    )
    (net (code "37") (name "Net-(C136-Pad2)") (class "Default")
      (node (ref "C136") (pin "2") (pinfunction "2_2") (pintype "passive"))
      (node (ref "R184") (pin "1") (pinfunction "1_1") (pintype "passive"))
      (node (ref "X6") (pin "1") (pinfunction "1_1") (pintype "passive"))
    )
    (net (code "38") (name "Net-(C139-Pad2)") (class "Default")
      (node (ref "C139") (pin "2") (pinfunction "2_2") (pintype "passive"))
      (node (ref "R190") (pin "1") (pinfunction "1_1") (pintype "passive"))
      (node (ref "X6") (pin "3") (pinfunction "3_3") (pintype "passive"))
    )
    (net (code "39") (name "Net-(CN18-CT1)") (class "Default")
      (node (ref "C154") (pin "2") (pinfunction "2_2") (pintype "passive"))
      (node (ref "CN18") (pin "5") (pinfunction "CT1_5") (pintype "passive"))
      (node (ref "CN18") (pin "6") (pinfunction "CT2_6") (pintype "passive"))
    )
    (net (code "40") (name "Net-(CN18-GA)") (class "Default")
      (node (ref "CN18") (pin "11") (pinfunction "GA_11") (pintype "passive"))
      (node (ref "R237") (pin "1") (pinfunction "1_1") (pintype "passive"))
    )
    (net (code "41") (name "Net-(CN18-GC)") (class "Default")
      (node (ref "CN18") (pin "12") (pinfunction "GC_12") (pintype "passive"))
      (node (ref "R315") (pin "2") (pinfunction "2_2") (pintype "passive"))
      (node (ref "U40") (pin "32") (pinfunction "LED0_CFG_EXT_32") (pintype "bidirectional"))
    )
    (net (code "42") (name "Net-(CN18-YA)") (class "Default")
      (node (ref "CN18") (pin "13") (pinfunction "YA_13") (pintype "passive"))
      (node (ref "R320") (pin "2") (pinfunction "2_2") (pintype "passive"))
      (node (ref "U40") (pin "33") (pinfunction "LED1_CFG_LD0_33") (pintype "bidirectional"))
    )
    (net (code "43") (name "Net-(CN18-YC)") (class "Default")
      (node (ref "CN18") (pin "14") (pinfunction "YC_14") (pintype "passive"))
      (node (ref "R238") (pin "2") (pinfunction "2_2") (pintype "passive"))
    )
    (net (code "44") (name "Net-(LD9-Pad2)") (class "Default")
      (node (ref "LD9") (pin "2") (pintype "passive"))
      (node (ref "R128") (pin "1") (pinfunction "1_1") (pintype "passive"))
    )
    (net (code "45") (name "Net-(U40-CLKOUT)") (class "Default")
      (node (ref "TP31") (pin "1") (pinfunction "1_1") (pintype "passive"))
      (node (ref "U40") (pin "35") (pinfunction "CLKOUT_35") (pintype "output"))
    )
    (net (code "46") (name "Net-(U40-LED2_CFG_LDO1)") (class "Default")
      (node (ref "LD9") (pin "1") (pintype "passive"))
      (node (ref "R160") (pin "2") (pinfunction "2_2") (pintype "passive"))
      (node (ref "U40") (pin "34") (pinfunction "LED2_CFG_LDO1_34") (pintype "output"))
    )
    (net (code "47") (name "Net-(U40-REG_OUT)") (class "Default")
      (node (ref "LE3") (pin "1") (pinfunction "1_1") (pintype "passive"))
      (node (ref "U40") (pin "30") (pinfunction "REG_OUT_30") (pintype "output"))
    )
    (net (code "48") (name "Net-(U40-RSET)") (class "Default")
      (node (ref "R201") (pin "1") (pinfunction "1_1") (pintype "passive"))
      (node (ref "U40") (pin "39") (pinfunction "RSET_39") (pintype "output"))
    )
    (net (code "49") (name "Net-(U40-RXCLK_PHYAD1)") (class "Default")
      (node (ref "R147") (pin "2") (pinfunction "2_2") (pintype "passive"))
      (node (ref "U40") (pin "27") (pinfunction "RXCLK_PHYAD1_27") (pintype "passive"))
    )
    (net (code "50") (name "Net-(U40-RXCTL_PHYAD2)") (class "Default")
      (node (ref "R148") (pin "2") (pinfunction "2_2") (pintype "passive"))
      (node (ref "U40") (pin "26") (pinfunction "RXCTL_PHYAD2_26") (pintype "passive"))
    )
    (net (code "51") (name "Net-(U40-RXD0_RXDLY)") (class "Default")
      (node (ref "R149") (pin "2") (pinfunction "2_2") (pintype "passive"))
      (node (ref "U40") (pin "25") (pinfunction "RXD0_RXDLY_25") (pintype "output"))
    )
    (net (code "52") (name "Net-(U40-RXD1_TXDLY)") (class "Default")
      (node (ref "R150") (pin "2") (pinfunction "2_2") (pintype "passive"))
      (node (ref "U40") (pin "24") (pinfunction "RXD1_TXDLY_24") (pintype "output"))
    )
    (net (code "53") (name "Net-(U40-RXD2_PLLOFF)") (class "Default")
      (node (ref "R151") (pin "2") (pinfunction "2_2") (pintype "passive"))
      (node (ref "U40") (pin "23") (pinfunction "RXD2_PLLOFF_23") (pintype "output"))
    )
    (net (code "54") (name "Net-(U40-RXD3_PHYAD0)") (class "Default")
      (node (ref "R152") (pin "2") (pinfunction "2_2") (pintype "passive"))
      (node (ref "U40") (pin "22") (pinfunction "RXD3_PHYAD0_22") (pintype "output"))
    )
    (net (code "55") (name "Net-(U40-TXCLK)") (class "Default")
      (node (ref "R163") (pin "2") (pinfunction "2_2") (pintype "passive"))
      (node (ref "U40") (pin "20") (pinfunction "TXCLK_20") (pintype "input"))
    )
    (net (code "56") (name "Net-(U40-TXCTL)") (class "Default")
      (node (ref "R166") (pin "2") (pinfunction "2_2") (pintype "passive"))
      (node (ref "U40") (pin "19") (pinfunction "TXCTL_19") (pintype "input"))
    )
    (net (code "57") (name "Net-(U40-TXD0)") (class "Default")
      (node (ref "R169") (pin "2") (pinfunction "2_2") (pintype "passive"))
      (node (ref "U40") (pin "18") (pinfunction "TXD0_18") (pintype "input"))
    )
    (net (code "58") (name "Net-(U40-TXD1)") (class "Default")
      (node (ref "R175") (pin "2") (pinfunction "2_2") (pintype "passive"))
      (node (ref "U40") (pin "17") (pinfunction "TXD1_17") (pintype "input"))
    )
    (net (code "59") (name "Net-(U40-TXD2)") (class "Default")
      (node (ref "R180") (pin "2") (pinfunction "2_2") (pintype "passive"))
      (node (ref "U40") (pin "16") (pinfunction "TXD2_16") (pintype "input"))
    )
    (net (code "60") (name "Net-(U40-TXD3)") (class "Default")
      (node (ref "R187") (pin "2") (pinfunction "2_2") (pintype "passive"))
      (node (ref "U40") (pin "15") (pinfunction "TXD3_15") (pintype "input"))
    )
    (net (code "61") (name "Net-(U40-XTAL_IN)") (class "Default")
      (node (ref "R184") (pin "2") (pinfunction "2_2") (pintype "passive"))
      (node (ref "U40") (pin "36") (pinfunction "XTAL_IN_36") (pintype "input"))
    )
    (net (code "62") (name "Net-(U40-XTAL_OUT_EXT_CLK)") (class "Default")
      (node (ref "R190") (pin "2") (pinfunction "2_2") (pintype "passive"))
      (node (ref "R198") (pin "2") (pinfunction "2_2") (pintype "passive"))
      (node (ref "U40") (pin "37") (pinfunction "XTAL_OUT_EXT_CLK_37") (pintype "output"))
    )
  )
)
